# Schematic_1.net
KiCad netlist of a schematic drawn in Altium Designer
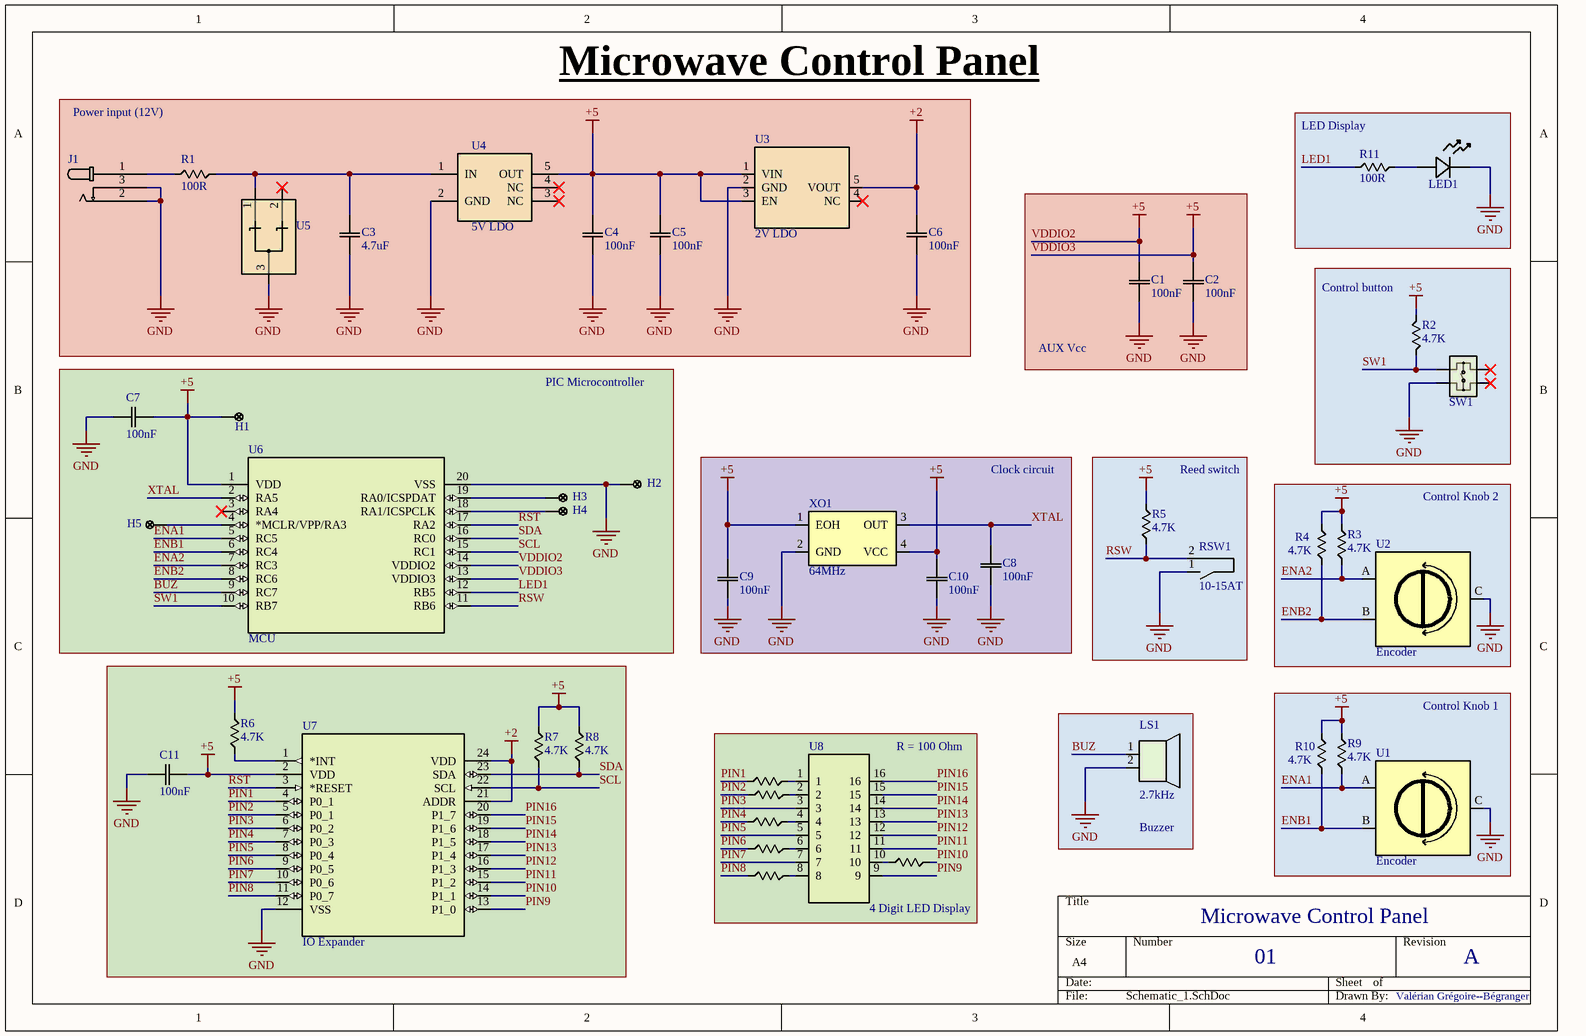
[diagram p0: Schematic_1.SchDoc]

(export (version "E")
  (design (tool "Eeschema 10.0.6"))
  (components
    (comp (ref "C1")
      (value "100nF")
      (footprint "0805_AVX")
      (libsource (lib "Schematic_Library_1") (part "08051C103JAT2A"))
    )
    (comp (ref "C2")
      (value "100nF")
      (footprint "0805_AVX")
      (libsource (lib "Schematic_Library_1") (part "08051C103JAT2A"))
    )
    (comp (ref "C3")
      (value "4.7uF")
      (footprint "CAP_08051A0R8CAT2A_AVX")
      (libsource (lib "Schematic_Library_1") (part "08053C472K4Z2A"))
    )
    (comp (ref "C4")
      (value "100nF")
      (footprint "0805_AVX")
      (libsource (lib "Schematic_Library_1") (part "08051C103JAT2A"))
    )
    (comp (ref "C5")
      (value "100nF")
      (footprint "0805_AVX")
      (libsource (lib "Schematic_Library_1") (part "08051C103JAT2A"))
    )
    (comp (ref "C6")
      (value "100nF")
      (footprint "0805_AVX")
      (libsource (lib "Schematic_Library_1") (part "08051C103JAT2A"))
    )
    (comp (ref "C7")
      (value "100nF")
      (footprint "0805_AVX")
      (libsource (lib "Schematic_Library_1") (part "08051C103JAT2A"))
    )
    (comp (ref "C8")
      (value "100nF")
      (footprint "0805_AVX")
      (libsource (lib "Schematic_Library_1") (part "08051C103JAT2A"))
    )
    (comp (ref "C9")
      (value "100nF")
      (footprint "0805_AVX")
      (libsource (lib "Schematic_Library_1") (part "08051C103JAT2A"))
    )
    (comp (ref "C10")
      (value "100nF")
      (footprint "0805_AVX")
      (libsource (lib "Schematic_Library_1") (part "08051C103JAT2A"))
    )
    (comp (ref "C11")
      (value "100nF")
      (footprint "0805_AVX")
      (libsource (lib "Schematic_Library_1") (part "08051C103JAT2A"))
    )
    (comp (ref "H1")
      (value "Output")
      (footprint "1 pin header")
      (libsource (lib "Schematic_Library_1") (part "1 pin header"))
    )
    (comp (ref "H2")
      (value "Output")
      (footprint "1 pin header")
      (libsource (lib "Schematic_Library_1") (part "1 pin header"))
    )
    (comp (ref "H3")
      (value "Output")
      (footprint "1 pin header")
      (libsource (lib "Schematic_Library_1") (part "1 pin header"))
    )
    (comp (ref "H4")
      (value "Output")
      (footprint "1 pin header")
      (libsource (lib "Schematic_Library_1") (part "1 pin header"))
    )
    (comp (ref "H5")
      (value "Output")
      (footprint "1 pin header")
      (libsource (lib "Schematic_Library_1") (part "1 pin header"))
    )
    (comp (ref "J1")
      (value "PJ-002A")
      (footprint "PJ-002A_CUD")
      (description "DC power plug")
      (libsource (lib "Schematic_Library_1") (part "PJ-002A"))
    )
    (comp (ref "LED1")
      (value "156120VS75300")
      (footprint "LED_VS75300_WRE")
      (description "LED")
      (libsource (lib "Schematic_Library_1") (part "156120VS75300"))
    )
    (comp (ref "LS1")
      (value "2.7kHz")
      (footprint "CMI-9605IC_CUD")
      (description "Buzzer")
      (libsource (lib "Schematic_Library_1") (part "CMI-9605IC-0380T"))
    )
    (comp (ref "R1")
      (value "100R")
      (footprint "0805_VIS")
      (libsource (lib "Schematic_Library_1") (part "RCG080510R0FKEA"))
    )
    (comp (ref "R2")
      (value "4.7K")
      (footprint "RES_1220_SUS")
      (libsource (lib "Schematic_Library_1") (part "RG2012P-472-B-T5"))
    )
    (comp (ref "R3")
      (value "4.7K")
      (footprint "RES_1220_SUS")
      (libsource (lib "Schematic_Library_1") (part "RG2012P-472-B-T5"))
    )
    (comp (ref "R4")
      (value "4.7K")
      (footprint "RES_1220_SUS")
      (libsource (lib "Schematic_Library_1") (part "RG2012P-472-B-T5"))
    )
    (comp (ref "R5")
      (value "4.7K")
      (footprint "RES_1220_SUS")
      (libsource (lib "Schematic_Library_1") (part "RG2012P-472-B-T5"))
    )
    (comp (ref "R6")
      (value "4.7K")
      (footprint "RES_1220_SUS")
      (libsource (lib "Schematic_Library_1") (part "RG2012P-472-B-T5"))
    )
    (comp (ref "R7")
      (value "4.7K")
      (footprint "RES_1220_SUS")
      (libsource (lib "Schematic_Library_1") (part "RG2012P-472-B-T5"))
    )
    (comp (ref "R8")
      (value "4.7K")
      (footprint "RES_1220_SUS")
      (libsource (lib "Schematic_Library_1") (part "RG2012P-472-B-T5"))
    )
    (comp (ref "R9")
      (value "4.7K")
      (footprint "RES_1220_SUS")
      (libsource (lib "Schematic_Library_1") (part "RG2012P-472-B-T5"))
    )
    (comp (ref "R10")
      (value "4.7K")
      (footprint "RES_1220_SUS")
      (libsource (lib "Schematic_Library_1") (part "RG2012P-472-B-T5"))
    )
    (comp (ref "R11")
      (value "100R")
      (footprint "0805_VIS")
      (libsource (lib "Schematic_Library_1") (part "RCG080510R0FKEA"))
    )
    (comp (ref "R12")
      (value "100R")
      (footprint "0805_VIS")
      (libsource (lib "Schematic_Library_1") (part "RCG080510R0FKEA"))
    )
    (comp (ref "R13")
      (value "100R")
      (footprint "0805_VIS")
      (libsource (lib "Schematic_Library_1") (part "RCG080510R0FKEA"))
    )
    (comp (ref "R14")
      (value "100R")
      (footprint "0805_VIS")
      (libsource (lib "Schematic_Library_1") (part "RCG080510R0FKEA"))
    )
    (comp (ref "R15")
      (value "100R")
      (footprint "0805_VIS")
      (libsource (lib "Schematic_Library_1") (part "RCG080510R0FKEA"))
    )
    (comp (ref "R16")
      (value "100R")
      (footprint "0805_VIS")
      (libsource (lib "Schematic_Library_1") (part "RCG080510R0FKEA"))
    )
    (comp (ref "R17")
      (value "100R")
      (footprint "0805_VIS")
      (libsource (lib "Schematic_Library_1") (part "RCG080510R0FKEA"))
    )
    (comp (ref "RSW1")
      (value "10-15AT")
      (footprint "GP56010-15")
      (description "Reed switch")
      (libsource (lib "Schematic_Library_1") (part "GP56010-15"))
    )
    (comp (ref "SW1")
      (value "TS02-66-160-BK-100-LCR-D")
      (footprint "TS02-66-160-BK-100-LCR-D")
      (description "Push button")
      (libsource (lib "Schematic_Library_1") (part "TS02-66-160-BK-100-LCR-D"))
    )
    (comp (ref "U1")
      (value "Encoder")
      (footprint "288T232R161A1")
      (description "2b Encoder")
      (libsource (lib "Schematic_Library_1") (part "288T232R161A1"))
    )
    (comp (ref "U2")
      (value "Encoder")
      (footprint "288T232R161A1")
      (description "2b Encoder")
      (libsource (lib "Schematic_Library_1") (part "288T232R161A1"))
    )
    (comp (ref "U3")
      (value "2V LDO")
      (footprint "SC-70_C5_MCH")
      (libsource (lib "Schematic_Library_1") (part "MIC5365-2.0YC5-TR"))
    )
    (comp (ref "U4")
      (value "5V LDO")
      (footprint "SOT-23-5-DBV_TEX")
      (libsource (lib "Schematic_Library_1") (part "TPS7B92050DBVR"))
    )
    (comp (ref "U5")
      (value "MMBZ16VAT-QR")
      (footprint "SOT_SM712")
      (description "13V TVS")
      (libsource (lib "Schematic_Library_1") (part "MMBZ16VAT-QR"))
    )
    (comp (ref "U6")
      (value "MCU")
      (footprint "SOIC20_SO_MCH")
      (description "PIC MCU")
      (libsource (lib "Schematic_Library_1") (part "PIC18F15Q20T-ISO"))
    )
    (comp (ref "U7")
      (value "IO Expander")
      (footprint "TSSOP24_4P5X7P9_NXP")
      (description "16 I/O expander")
      (libsource (lib "Schematic_Library_1") (part "PCAL6416APW"))
    )
    (comp (ref "U8")
      (value "LED Display")
      (footprint "TDCG1060M_VIS")
      (description "4 digit LED display")
      (libsource (lib "Schematic_Library_1") (part "TDCR1060M"))
    )
    (comp (ref "XO1")
      (value "64MHz")
      (footprint "CB3-3C-64M0000")
      (description "64MHz Clock")
      (libsource (lib "Schematic_Library_1") (part "CB3-3C-64M0000"))
    )
  )
  (nets
    (net (code "1") (name "+2") (class "Default")
      (node (ref "C6") (pin "2") (pinfunction "2_2") (pintype "passive"))
      (node (ref "U3") (pin "5") (pinfunction "VOUT_5") (pintype "passive"))
      (node (ref "U7") (pin "21") (pinfunction "ADDR_21") (pintype "passive"))
      (node (ref "U7") (pin "24") (pinfunction "VDD_24") (pintype "passive"))
    )
    (net (code "2") (name "+5") (class "Default")
      (node (ref "C1") (pin "2") (pinfunction "2_2") (pintype "passive"))
      (node (ref "C10") (pin "2") (pinfunction "2_2") (pintype "passive"))
      (node (ref "C11") (pin "2") (pinfunction "2_2") (pintype "passive"))
      (node (ref "C2") (pin "2") (pinfunction "2_2") (pintype "passive"))
      (node (ref "C4") (pin "2") (pinfunction "2_2") (pintype "passive"))
      (node (ref "C5") (pin "2") (pinfunction "2_2") (pintype "passive"))
      (node (ref "C7") (pin "2") (pinfunction "2_2") (pintype "passive"))
      (node (ref "C9") (pin "2") (pinfunction "2_2") (pintype "passive"))
      (node (ref "H1") (pin "1") (pinfunction "1_1") (pintype "passive"))
      (node (ref "R10") (pin "2") (pinfunction "2_2") (pintype "passive"))
      (node (ref "R2") (pin "2") (pinfunction "2_2") (pintype "passive"))
      (node (ref "R3") (pin "2") (pinfunction "2_2") (pintype "passive"))
      (node (ref "R4") (pin "2") (pinfunction "2_2") (pintype "passive"))
      (node (ref "R5") (pin "2") (pinfunction "2_2") (pintype "passive"))
      (node (ref "R6") (pin "2") (pinfunction "2_2") (pintype "passive"))
      (node (ref "R7") (pin "2") (pinfunction "2_2") (pintype "passive"))
      (node (ref "R8") (pin "2") (pinfunction "2_2") (pintype "passive"))
      (node (ref "R9") (pin "2") (pinfunction "2_2") (pintype "passive"))
      (node (ref "U3") (pin "1") (pinfunction "VIN_1") (pintype "passive"))
      (node (ref "U3") (pin "3") (pinfunction "EN_3") (pintype "passive"))
      (node (ref "U4") (pin "5") (pinfunction "OUT_5") (pintype "passive"))
      (node (ref "U6") (pin "1") (pinfunction "VDD_1") (pintype "passive"))
      (node (ref "U6") (pin "13") (pinfunction "VDDIO3_13") (pintype "bidirectional"))
      (node (ref "U6") (pin "14") (pinfunction "VDDIO2_14") (pintype "bidirectional"))
      (node (ref "U7") (pin "2") (pinfunction "VDD_2") (pintype "passive"))
      (node (ref "XO1") (pin "1") (pinfunction "EOH_1") (pintype "passive"))
      (node (ref "XO1") (pin "4") (pinfunction "VCC_4") (pintype "passive"))
    )
    (net (code "3") (name "/BUZ") (class "Default")
      (node (ref "LS1") (pin "1") (pinfunction "1_1") (pintype "passive"))
      (node (ref "U6") (pin "9") (pinfunction "RC7_9") (pintype "bidirectional"))
    )
    (net (code "4") (name "/ENA1") (class "Default")
      (node (ref "R9") (pin "1") (pinfunction "1_1") (pintype "passive"))
      (node (ref "U1") (pin "A") (pinfunction "A_A") (pintype "passive"))
      (node (ref "U6") (pin "5") (pinfunction "RC5_5") (pintype "bidirectional"))
    )
    (net (code "5") (name "/ENA2") (class "Default")
      (node (ref "R3") (pin "1") (pinfunction "1_1") (pintype "passive"))
      (node (ref "U2") (pin "A") (pinfunction "A_A") (pintype "passive"))
      (node (ref "U6") (pin "7") (pinfunction "RC3_7") (pintype "bidirectional"))
    )
    (net (code "6") (name "/ENB1") (class "Default")
      (node (ref "R10") (pin "1") (pinfunction "1_1") (pintype "passive"))
      (node (ref "U1") (pin "B") (pinfunction "B_B") (pintype "passive"))
      (node (ref "U6") (pin "6") (pinfunction "RC4_6") (pintype "bidirectional"))
    )
    (net (code "7") (name "/ENB2") (class "Default")
      (node (ref "R4") (pin "1") (pinfunction "1_1") (pintype "passive"))
      (node (ref "U2") (pin "B") (pinfunction "B_B") (pintype "passive"))
      (node (ref "U6") (pin "8") (pinfunction "RC6_8") (pintype "bidirectional"))
    )
    (net (code "8") (name "/LED1") (class "Default")
      (node (ref "R11") (pin "1") (pinfunction "1_1") (pintype "passive"))
      (node (ref "U6") (pin "12") (pinfunction "RB5_12") (pintype "bidirectional"))
    )
    (net (code "9") (name "/PIN1") (class "Default")
      (node (ref "R12") (pin "1") (pinfunction "1_1") (pintype "passive"))
      (node (ref "U7") (pin "4") (pinfunction "P0_1_4") (pintype "bidirectional"))
    )
    (net (code "10") (name "/PIN2") (class "Default")
      (node (ref "R13") (pin "1") (pinfunction "1_1") (pintype "passive"))
      (node (ref "U7") (pin "5") (pinfunction "P0_1_5") (pintype "bidirectional"))
    )
    (net (code "11") (name "/PIN3") (class "Default")
      (node (ref "U7") (pin "6") (pinfunction "P0_2_6") (pintype "bidirectional"))
      (node (ref "U8") (pin "3") (pinfunction "3_3") (pintype "passive"))
    )
    (net (code "12") (name "/PIN4") (class "Default")
      (node (ref "R14") (pin "1") (pinfunction "1_1") (pintype "passive"))
      (node (ref "U7") (pin "7") (pinfunction "P0_3_7") (pintype "bidirectional"))
    )
    (net (code "13") (name "/PIN5") (class "Default")
      (node (ref "U7") (pin "8") (pinfunction "P0_4_8") (pintype "bidirectional"))
      (node (ref "U8") (pin "5") (pinfunction "5_5") (pintype "passive"))
    )
    (net (code "14") (name "/PIN6") (class "Default")
      (node (ref "R15") (pin "1") (pinfunction "1_1") (pintype "passive"))
      (node (ref "U7") (pin "9") (pinfunction "P0_5_9") (pintype "bidirectional"))
    )
    (net (code "15") (name "/PIN7") (class "Default")
      (node (ref "U7") (pin "10") (pinfunction "P0_6_10") (pintype "bidirectional"))
      (node (ref "U8") (pin "7") (pinfunction "7_7") (pintype "passive"))
    )
    (net (code "16") (name "/PIN8") (class "Default")
      (node (ref "R17") (pin "1") (pinfunction "1_1") (pintype "passive"))
      (node (ref "U7") (pin "11") (pinfunction "P0_7_11") (pintype "bidirectional"))
    )
    (net (code "17") (name "/PIN9") (class "Default")
      (node (ref "U7") (pin "13") (pinfunction "P1_0_13") (pintype "bidirectional"))
      (node (ref "U8") (pin "9") (pinfunction "9_9") (pintype "passive"))
    )
    (net (code "18") (name "/PIN10") (class "Default")
      (node (ref "R16") (pin "2") (pinfunction "2_2") (pintype "passive"))
      (node (ref "U7") (pin "14") (pinfunction "P1_1_14") (pintype "bidirectional"))
    )
    (net (code "19") (name "/PIN11") (class "Default")
      (node (ref "U7") (pin "15") (pinfunction "P1_2_15") (pintype "bidirectional"))
      (node (ref "U8") (pin "11") (pinfunction "11_11") (pintype "passive"))
    )
    (net (code "20") (name "/PIN12") (class "Default")
      (node (ref "U7") (pin "16") (pinfunction "P1_3_16") (pintype "bidirectional"))
      (node (ref "U8") (pin "12") (pinfunction "12_12") (pintype "passive"))
    )
    (net (code "21") (name "/PIN13") (class "Default")
      (node (ref "U7") (pin "17") (pinfunction "P1_4_17") (pintype "bidirectional"))
      (node (ref "U8") (pin "13") (pinfunction "13_13") (pintype "passive"))
    )
    (net (code "22") (name "/PIN14") (class "Default")
      (node (ref "U7") (pin "18") (pinfunction "P1_5_18") (pintype "bidirectional"))
      (node (ref "U8") (pin "14") (pinfunction "14_14") (pintype "passive"))
    )
    (net (code "23") (name "/PIN15") (class "Default")
      (node (ref "U7") (pin "19") (pinfunction "P1_6_19") (pintype "bidirectional"))
      (node (ref "U8") (pin "15") (pinfunction "15_15") (pintype "passive"))
    )
    (net (code "24") (name "/PIN16") (class "Default")
      (node (ref "U7") (pin "20") (pinfunction "P1_7_20") (pintype "bidirectional"))
      (node (ref "U8") (pin "16") (pinfunction "16_16") (pintype "passive"))
    )
    (net (code "25") (name "/RST") (class "Default")
      (node (ref "U6") (pin "17") (pinfunction "RA2_17") (pintype "bidirectional"))
      (node (ref "U7") (pin "3") (pinfunction "*RESET_3") (pintype "input"))
    )
    (net (code "26") (name "/RSW") (class "Default")
      (node (ref "R5") (pin "1") (pinfunction "1_1") (pintype "passive"))
      (node (ref "RSW1") (pin "2") (pinfunction "2_2") (pintype "passive"))
      (node (ref "U6") (pin "11") (pinfunction "RB6_11") (pintype "bidirectional"))
    )
    (net (code "27") (name "/SCL") (class "Default")
      (node (ref "R7") (pin "1") (pinfunction "1_1") (pintype "passive"))
      (node (ref "U6") (pin "15") (pinfunction "RC1_15") (pintype "bidirectional"))
      (node (ref "U7") (pin "22") (pinfunction "SCL_22") (pintype "input"))
    )
    (net (code "28") (name "/SDA") (class "Default")
      (node (ref "R8") (pin "1") (pinfunction "1_1") (pintype "passive"))
      (node (ref "U6") (pin "16") (pinfunction "RC0_16") (pintype "bidirectional"))
      (node (ref "U7") (pin "23") (pinfunction "SDA_23") (pintype "bidirectional"))
    )
    (net (code "29") (name "/SW1") (class "Default")
      (node (ref "R2") (pin "1") (pinfunction "1_1") (pintype "passive"))
      (node (ref "SW1") (pin "1") (pinfunction "2_1") (pintype "passive"))
      (node (ref "U6") (pin "10") (pinfunction "RB7_10") (pintype "bidirectional"))
    )
    (net (code "30") (name "/XTAL") (class "Default")
      (node (ref "C8") (pin "2") (pinfunction "2_2") (pintype "passive"))
      (node (ref "U6") (pin "2") (pinfunction "RA5_2") (pintype "bidirectional"))
      (node (ref "XO1") (pin "3") (pinfunction "OUT_3") (pintype "passive"))
    )
    (net (code "31") (name "GND") (class "Default")
      (node (ref "C1") (pin "1") (pinfunction "1_1") (pintype "passive"))
      (node (ref "C10") (pin "1") (pinfunction "1_1") (pintype "passive"))
      (node (ref "C11") (pin "1") (pinfunction "1_1") (pintype "passive"))
      (node (ref "C2") (pin "1") (pinfunction "1_1") (pintype "passive"))
      (node (ref "C3") (pin "1") (pinfunction "1_1") (pintype "passive"))
      (node (ref "C4") (pin "1") (pinfunction "1_1") (pintype "passive"))
      (node (ref "C5") (pin "1") (pinfunction "1_1") (pintype "passive"))
      (node (ref "C6") (pin "1") (pinfunction "1_1") (pintype "passive"))
      (node (ref "C7") (pin "1") (pinfunction "1_1") (pintype "passive"))
      (node (ref "C8") (pin "1") (pinfunction "1_1") (pintype "passive"))
      (node (ref "C9") (pin "1") (pinfunction "1_1") (pintype "passive"))
      (node (ref "H2") (pin "1") (pinfunction "1_1") (pintype "passive"))
      (node (ref "J1") (pin "2") (pinfunction "2_2") (pintype "passive"))
      (node (ref "J1") (pin "3") (pinfunction "3_3") (pintype "passive"))
      (node (ref "LED1") (pin "1") (pinfunction "1_1") (pintype "passive"))
      (node (ref "LS1") (pin "2") (pinfunction "2_2") (pintype "passive"))
      (node (ref "RSW1") (pin "1") (pinfunction "1_1") (pintype "passive"))
      (node (ref "SW1") (pin "2") (pinfunction "4_2") (pintype "passive"))
      (node (ref "U1") (pin "C") (pinfunction "C_C") (pintype "passive"))
      (node (ref "U2") (pin "C") (pinfunction "C_C") (pintype "passive"))
      (node (ref "U3") (pin "2") (pinfunction "GND_2") (pintype "power_in"))
      (node (ref "U4") (pin "2") (pinfunction "GND_2") (pintype "power_in"))
      (node (ref "U5") (pin "3") (pinfunction "3_3") (pintype "passive"))
      (node (ref "U6") (pin "20") (pinfunction "VSS_20") (pintype "passive"))
      (node (ref "U7") (pin "12") (pinfunction "VSS_12") (pintype "power_in"))
      (node (ref "XO1") (pin "2") (pinfunction "GND_2") (pintype "passive"))
    )
    (net (code "32") (name "Net-(J1-Pad1)") (class "Default")
      (node (ref "J1") (pin "1") (pinfunction "1_1") (pintype "passive"))
      (node (ref "R1") (pin "1") (pinfunction "1_1") (pintype "passive"))
    )
    (net (code "33") (name "Net-(LED1-Pad2)") (class "Default")
      (node (ref "LED1") (pin "2") (pinfunction "2_2") (pintype "passive"))
      (node (ref "R11") (pin "2") (pinfunction "2_2") (pintype "passive"))
    )
    (net (code "34") (name "Net-(R12-Pad2)") (class "Default")
      (node (ref "R12") (pin "2") (pinfunction "2_2") (pintype "passive"))
      (node (ref "U8") (pin "1") (pinfunction "1_1") (pintype "passive"))
    )
    (net (code "35") (name "Net-(R13-Pad2)") (class "Default")
      (node (ref "R13") (pin "2") (pinfunction "2_2") (pintype "passive"))
      (node (ref "U8") (pin "2") (pinfunction "2_2") (pintype "passive"))
    )
    (net (code "36") (name "Net-(R14-Pad2)") (class "Default")
      (node (ref "R14") (pin "2") (pinfunction "2_2") (pintype "passive"))
      (node (ref "U8") (pin "4") (pinfunction "4_4") (pintype "passive"))
    )
    (net (code "37") (name "Net-(R15-Pad2)") (class "Default")
      (node (ref "R15") (pin "2") (pinfunction "2_2") (pintype "passive"))
      (node (ref "U8") (pin "6") (pinfunction "6_6") (pintype "passive"))
    )
    (net (code "38") (name "Net-(R16-Pad1)") (class "Default")
      (node (ref "R16") (pin "1") (pinfunction "1_1") (pintype "passive"))
      (node (ref "U8") (pin "10") (pinfunction "10_10") (pintype "passive"))
    )
    (net (code "39") (name "Net-(R17-Pad2)") (class "Default")
      (node (ref "R17") (pin "2") (pinfunction "2_2") (pintype "passive"))
      (node (ref "U8") (pin "8") (pinfunction "8_8") (pintype "passive"))
    )
    (net (code "40") (name "Net-(U4-IN)") (class "Default")
      (node (ref "C3") (pin "2") (pinfunction "2_2") (pintype "passive"))
      (node (ref "R1") (pin "2") (pinfunction "2_2") (pintype "passive"))
      (node (ref "U4") (pin "1") (pinfunction "IN_1") (pintype "passive"))
      (node (ref "U5") (pin "1") (pinfunction "1_1") (pintype "passive"))
    )
    (net (code "41") (name "Net-(U6-*MCLR{slash}VPP{slash}RA3)") (class "Default")
      (node (ref "H5") (pin "1") (pinfunction "1_1") (pintype "passive"))
      (node (ref "U6") (pin "4") (pinfunction "*MCLR/VPP/RA3_4") (pintype "bidirectional"))
    )
    (net (code "42") (name "Net-(U6-RA0{slash}ICSPDAT)") (class "Default")
      (node (ref "H3") (pin "1") (pinfunction "1_1") (pintype "passive"))
      (node (ref "U6") (pin "19") (pinfunction "RA0/ICSPDAT_19") (pintype "bidirectional"))
    )
    (net (code "43") (name "Net-(U6-RA1{slash}ICSPCLK)") (class "Default")
      (node (ref "H4") (pin "1") (pinfunction "1_1") (pintype "passive"))
      (node (ref "U6") (pin "18") (pinfunction "RA1/ICSPCLK_18") (pintype "bidirectional"))
    )
    (net (code "44") (name "Net-(U7-*INT)") (class "Default")
      (node (ref "R6") (pin "1") (pinfunction "1_1") (pintype "passive"))
      (node (ref "U7") (pin "1") (pinfunction "*INT_1") (pintype "output"))
    )
    (net (code "45") (name "unconnected-(SW1-3-Pad2)") (class "Default")
      (node (ref "SW1") (pin "2") (pinfunction "3_2") (pintype "passive+no_connect"))
    )
    (net (code "46") (name "unconnected-(SW1-Pad1)") (class "Default")
      (node (ref "SW1") (pin "1") (pinfunction "1_1") (pintype "passive+no_connect"))
    )
    (net (code "47") (name "unconnected-(U3-NC-Pad4)") (class "Default")
      (node (ref "U3") (pin "4") (pinfunction "NC_4") (pintype "passive+no_connect"))
    )
    (net (code "48") (name "unconnected-(U4-NC-Pad3)") (class "Default")
      (node (ref "U4") (pin "3") (pinfunction "NC_3") (pintype "passive+no_connect"))
    )
    (net (code "49") (name "unconnected-(U4-NC-Pad4)") (class "Default")
      (node (ref "U4") (pin "4") (pinfunction "NC_4") (pintype "passive+no_connect"))
    )
    (net (code "50") (name "unconnected-(U5-Pad2)") (class "Default")
      (node (ref "U5") (pin "2") (pinfunction "2_2") (pintype "passive+no_connect"))
    )
    (net (code "51") (name "unconnected-(U6-RA4-Pad3)") (class "Default")
      (node (ref "U6") (pin "3") (pinfunction "RA4_3") (pintype "bidirectional+no_connect"))
    )
  )
)
